# taller_pcb.net
KiCad netlist of a schematic drawn in EAGLE
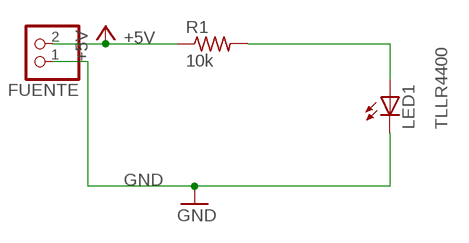
[diagram p0: schematic, sheet 1]

(export (version "E")
  (design (tool "Eeschema 10.0.6"))
  (components
    (comp (ref "FUENTE")
      (value "PINHD-1X2")
      (footprint "eagle-import:1X02")
      (libsource (lib "eagle-import") (part "PINHD-1X2"))
    )
    (comp (ref "LED1")
      (value "TLLR4400")
      (footprint "eagle-import:LED3MM")
      (fields (field (name "MF") "VISHAY SEMICONDUCTOR"))
      (libsource (lib "eagle-import") (part "TLLR4400"))
    )
    (comp (ref "R1")
      (value "10k")
      (footprint "eagle-import:0309_12")
      (libsource (lib "eagle-import") (part "R-US_0309/12"))
    )
  )
  (nets
    (net (code "1") (name "+5V") (class "Default")
      (node (ref "FUENTE") (pin "2") (pinfunction "2_2") (pintype "passive"))
      (node (ref "R1") (pin "1") (pinfunction "1_1") (pintype "passive"))
    )
    (net (code "2") (name "GND") (class "Default")
      (node (ref "FUENTE") (pin "1") (pinfunction "1_1") (pintype "passive"))
      (node (ref "LED1") (pin "K") (pinfunction "C_K") (pintype "passive"))
    )
    (net (code "3") (name "Net-(LED1-PadA)") (class "Default")
      (node (ref "LED1") (pin "A") (pinfunction "A_A") (pintype "passive"))
      (node (ref "R1") (pin "2") (pinfunction "2_2") (pintype "passive"))
    )
  )
)
